# basecontrol3.net
KiCad netlist of a schematic drawn in Altium Designer
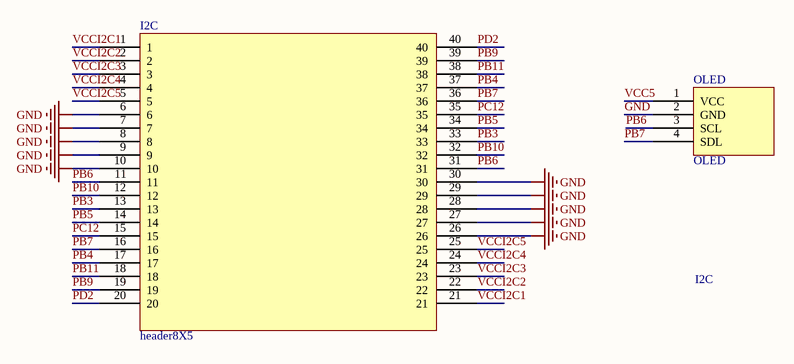
[diagram p0: basecontrol3.SchDoc]

(export (version "E")
  (design (tool "Eeschema 10.0.6"))
  (components
    (comp (ref "I2C")
      (value "header8X5")
      (footprint "header8X5")
      (libsource (lib "baseControl") (part "header8X5"))
    )
    (comp (ref "OLED")
      (value "OLED")
      (footprint "OLED_12864")
      (libsource (lib "controlBsae") (part "OLED_12864"))
    )
  )
  (nets
    (net (code "1") (name "/PB3") (class "Default")
      (node (ref "I2C") (pin "13") (pinfunction "13_13") (pintype "passive"))
      (node (ref "I2C") (pin "33") (pinfunction "33_33") (pintype "passive"))
    )
    (net (code "2") (name "/PB4") (class "Default")
      (node (ref "I2C") (pin "17") (pinfunction "17_17") (pintype "passive"))
      (node (ref "I2C") (pin "37") (pinfunction "37_37") (pintype "passive"))
    )
    (net (code "3") (name "/PB5") (class "Default")
      (node (ref "I2C") (pin "14") (pinfunction "14_14") (pintype "passive"))
      (node (ref "I2C") (pin "34") (pinfunction "34_34") (pintype "passive"))
    )
    (net (code "4") (name "/PB6") (class "Default")
      (node (ref "I2C") (pin "11") (pinfunction "11_11") (pintype "passive"))
      (node (ref "I2C") (pin "31") (pinfunction "31_31") (pintype "passive"))
      (node (ref "OLED") (pin "3") (pinfunction "SCL_3") (pintype "passive"))
    )
    (net (code "5") (name "/PB7") (class "Default")
      (node (ref "I2C") (pin "16") (pinfunction "16_16") (pintype "passive"))
      (node (ref "I2C") (pin "36") (pinfunction "36_36") (pintype "passive"))
      (node (ref "OLED") (pin "4") (pinfunction "SDL_4") (pintype "passive"))
    )
    (net (code "6") (name "/PB9") (class "Default")
      (node (ref "I2C") (pin "19") (pinfunction "19_19") (pintype "passive"))
      (node (ref "I2C") (pin "39") (pinfunction "39_39") (pintype "passive"))
    )
    (net (code "7") (name "/PB10") (class "Default")
      (node (ref "I2C") (pin "12") (pinfunction "12_12") (pintype "passive"))
      (node (ref "I2C") (pin "32") (pinfunction "32_32") (pintype "passive"))
    )
    (net (code "8") (name "/PB11") (class "Default")
      (node (ref "I2C") (pin "18") (pinfunction "18_18") (pintype "passive"))
      (node (ref "I2C") (pin "38") (pinfunction "38_38") (pintype "passive"))
    )
    (net (code "9") (name "/PC12") (class "Default")
      (node (ref "I2C") (pin "15") (pinfunction "15_15") (pintype "passive"))
      (node (ref "I2C") (pin "35") (pinfunction "35_35") (pintype "passive"))
    )
    (net (code "10") (name "/PD2") (class "Default")
      (node (ref "I2C") (pin "20") (pinfunction "20_20") (pintype "passive"))
      (node (ref "I2C") (pin "40") (pinfunction "40_40") (pintype "passive"))
    )
    (net (code "11") (name "/VCC5") (class "Default")
      (node (ref "OLED") (pin "1") (pinfunction "VCC_1") (pintype "passive"))
    )
    (net (code "12") (name "/VCCI2C1") (class "Default")
      (node (ref "I2C") (pin "1") (pinfunction "1_1") (pintype "passive"))
      (node (ref "I2C") (pin "21") (pinfunction "21_21") (pintype "passive"))
    )
    (net (code "13") (name "/VCCI2C2") (class "Default")
      (node (ref "I2C") (pin "2") (pinfunction "2_2") (pintype "passive"))
      (node (ref "I2C") (pin "22") (pinfunction "22_22") (pintype "passive"))
    )
    (net (code "14") (name "/VCCI2C3") (class "Default")
      (node (ref "I2C") (pin "23") (pinfunction "23_23") (pintype "passive"))
      (node (ref "I2C") (pin "3") (pinfunction "3_3") (pintype "passive"))
    )
    (net (code "15") (name "/VCCI2C4") (class "Default")
      (node (ref "I2C") (pin "24") (pinfunction "24_24") (pintype "passive"))
      (node (ref "I2C") (pin "4") (pinfunction "4_4") (pintype "passive"))
    )
    (net (code "16") (name "/VCCI2C5") (class "Default")
      (node (ref "I2C") (pin "25") (pinfunction "25_25") (pintype "passive"))
      (node (ref "I2C") (pin "5") (pinfunction "5_5") (pintype "passive"))
    )
    (net (code "17") (name "GND") (class "Default")
      (node (ref "I2C") (pin "10") (pinfunction "10_10") (pintype "passive"))
      (node (ref "I2C") (pin "26") (pinfunction "26_26") (pintype "passive"))
      (node (ref "I2C") (pin "27") (pinfunction "27_27") (pintype "passive"))
      (node (ref "I2C") (pin "28") (pinfunction "28_28") (pintype "passive"))
      (node (ref "I2C") (pin "29") (pinfunction "29_29") (pintype "passive"))
      (node (ref "I2C") (pin "30") (pinfunction "30_30") (pintype "passive"))
      (node (ref "I2C") (pin "6") (pinfunction "6_6") (pintype "passive"))
      (node (ref "I2C") (pin "7") (pinfunction "7_7") (pintype "passive"))
      (node (ref "I2C") (pin "8") (pinfunction "8_8") (pintype "passive"))
      (node (ref "I2C") (pin "9") (pinfunction "9_9") (pintype "passive"))
      (node (ref "OLED") (pin "2") (pinfunction "GND_2") (pintype "passive"))
    )
  )
)
